# mcu.net
KiCad netlist of a schematic drawn in Altium Designer
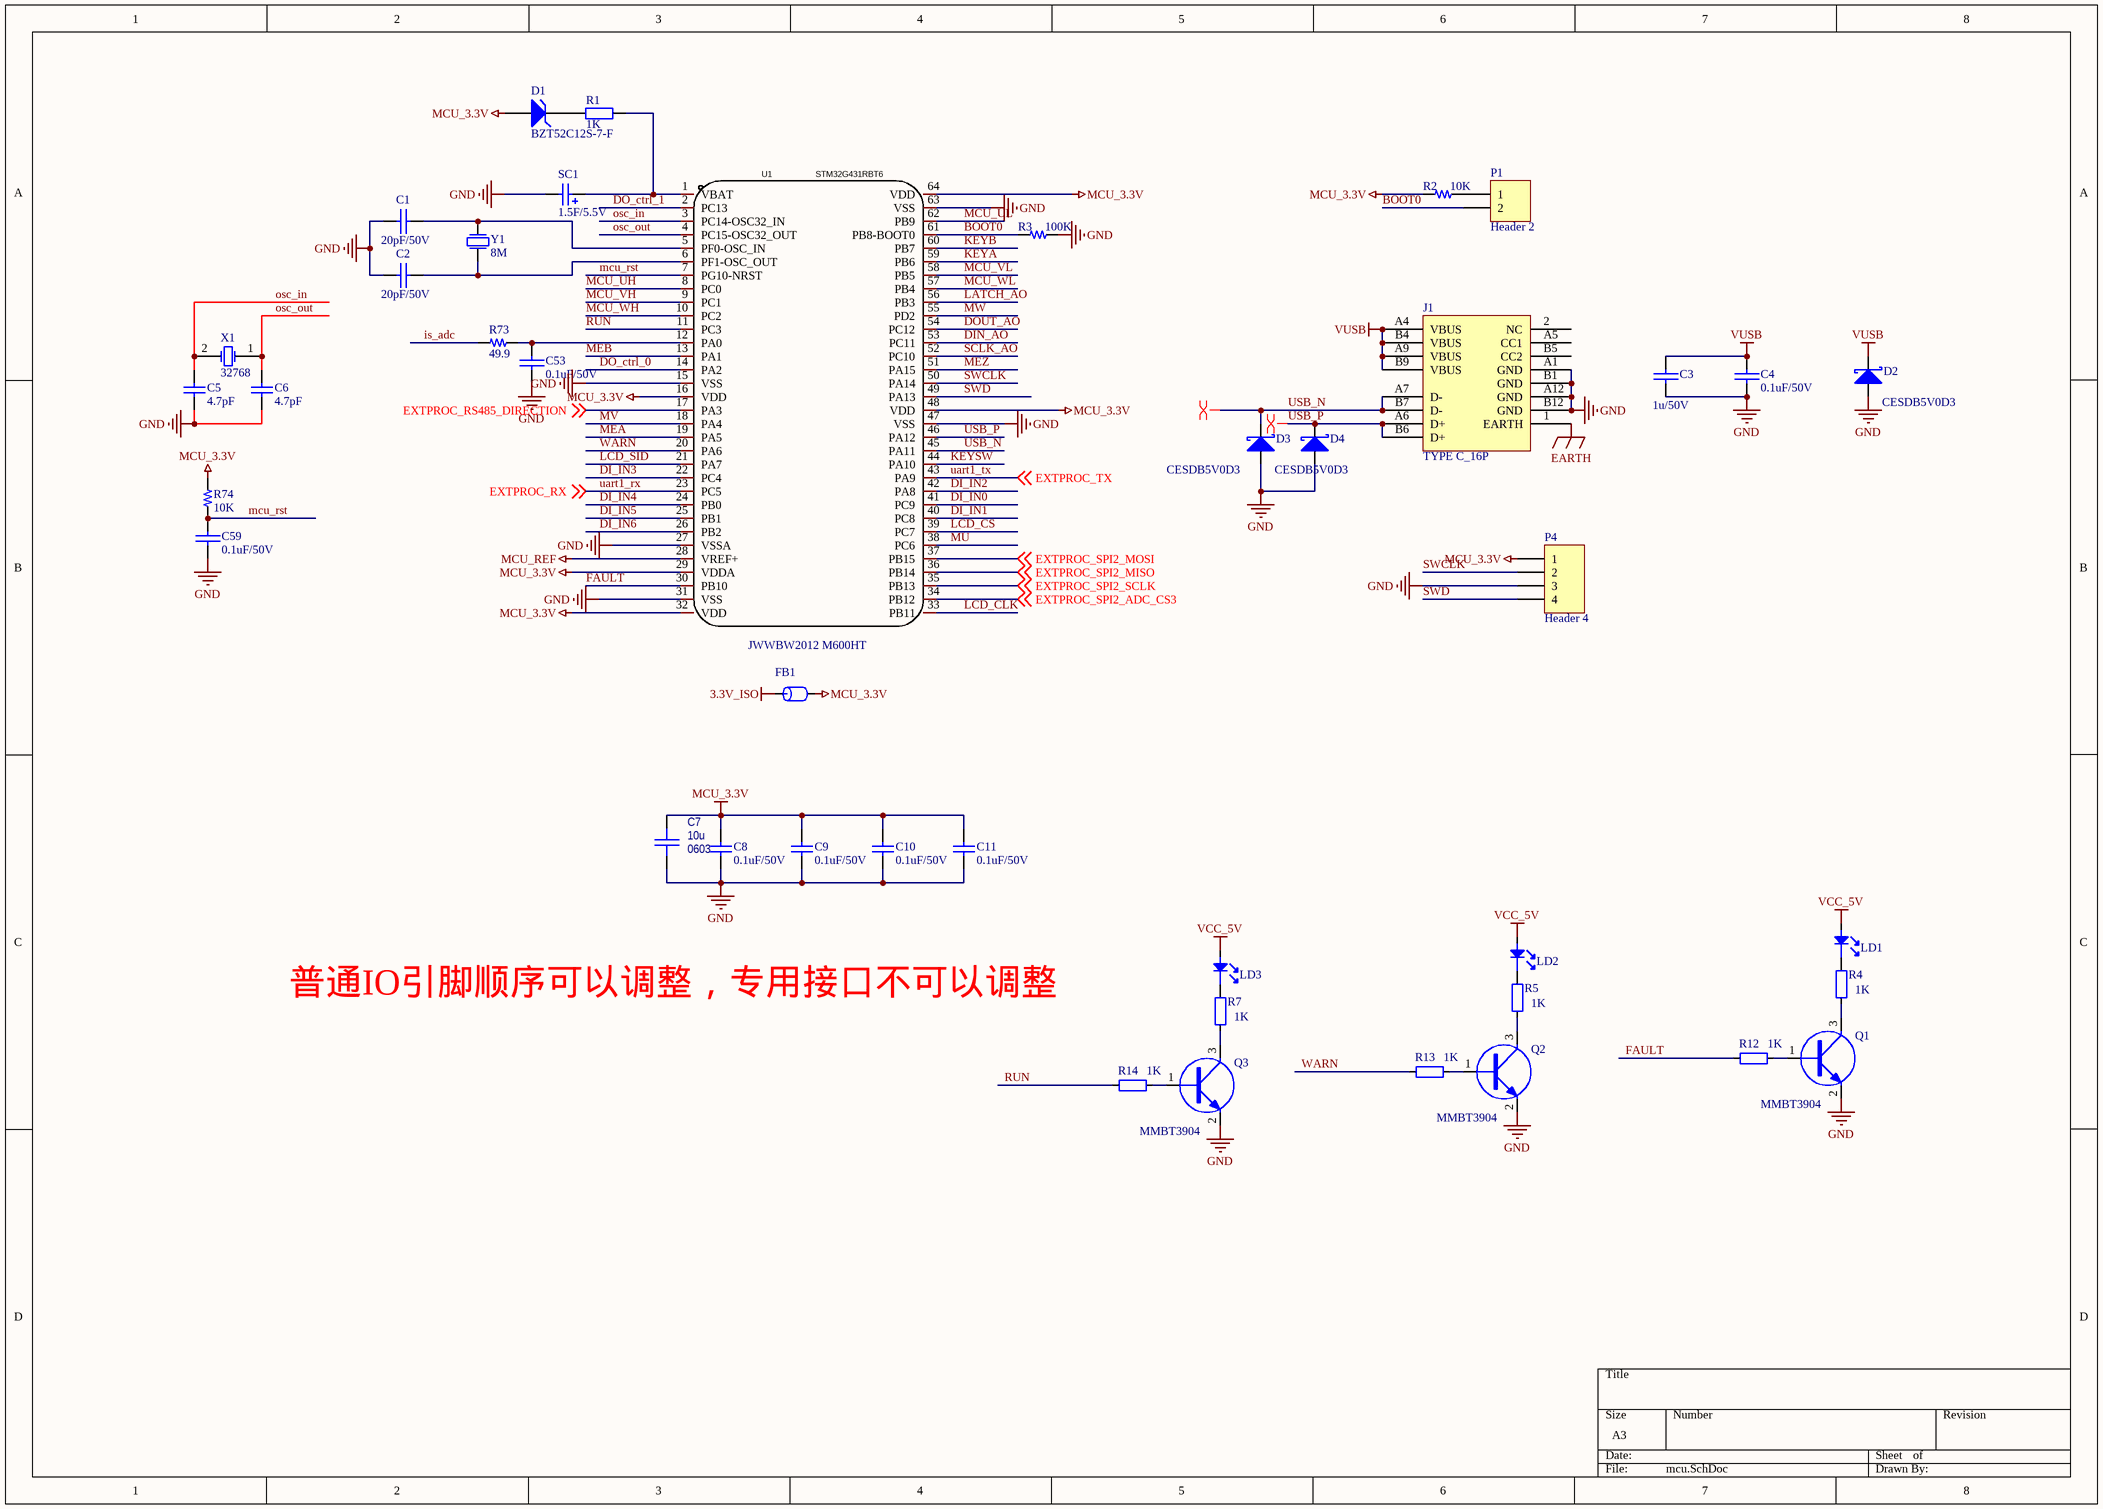
[diagram p0: mcu.SchDoc]

(export (version "E")
  (design (tool "Eeschema 10.0.6"))
  (components
    (comp (ref "C1")
      (value "20pF/50V")
      (footprint "0603C")
      (fields (field (name "Comment") "20pF/25V"))
      (libsource (lib "SM") (part "CAP"))
    )
    (comp (ref "C2")
      (value "20pF/50V")
      (footprint "0603C")
      (fields (field (name "Comment") "20pF/25V"))
      (libsource (lib "SM") (part "CAP"))
    )
    (comp (ref "C3")
      (value "1u/50V")
      (footprint "0603C")
      (fields (field (name "Comment") "1uF/25V"))
      (libsource (lib "SM") (part "CAP"))
    )
    (comp (ref "C4") (value "0.1uF/50V") (footprint "0603C") (libsource (lib "SM") (part "CAP")))
    (comp (ref "C5")
      (value "4.7pF")
      (footprint "0603C")
      (description "Capacitor")
      (fields (field (name "PUBLISHER") "Altium Limited"))
      (libsource (lib "Miscellaneous Devices") (part "Cap"))
    )
    (comp (ref "C6")
      (value "4.7pF")
      (footprint "0603C")
      (description "Capacitor")
      (fields (field (name "PUBLISHER") "Altium Limited"))
      (libsource (lib "Miscellaneous Devices") (part "Cap"))
    )
    (comp (ref "C7")
      (value "10u")
      (footprint "CAPC1608X092N_0603")
      (description "Capacitor, MLCC")
      (fields
        (field (name "MANUFACTURER") "Murata Electronics")
        (field (name "PARTNUMBER") "GRM188R61A106KE69D")
        (field (name "PACKAGE") "0603")
      )
      (libsource (lib "Karl") (part "Capacitor_0603"))
    )
    (comp (ref "C8")
      (value "0.1uF/50V")
      (footprint "0603C")
      (description "Capacitor")
      (fields (field (name "PUBLISHER") "Altium Limited"))
      (libsource (lib "Miscellaneous Devices") (part "Cap"))
    )
    (comp (ref "C9")
      (value "0.1uF/50V")
      (footprint "0603C")
      (description "Capacitor")
      (fields (field (name "PUBLISHER") "Altium Limited"))
      (libsource (lib "Miscellaneous Devices") (part "Cap"))
    )
    (comp (ref "C10")
      (value "0.1uF/50V")
      (footprint "0603C")
      (description "Capacitor")
      (fields (field (name "PUBLISHER") "Altium Limited"))
      (libsource (lib "Miscellaneous Devices") (part "Cap"))
    )
    (comp (ref "C11")
      (value "0.1uF/50V")
      (footprint "0603C")
      (description "Capacitor")
      (fields (field (name "PUBLISHER") "Altium Limited"))
      (libsource (lib "Miscellaneous Devices") (part "Cap"))
    )
    (comp (ref "C53") (value "0.1uF/50V") (footprint "0603C") (libsource (lib "SM") (part "CAP")))
    (comp (ref "C59") (value "0.1uF/50V") (footprint "0603C") (libsource (lib "SM") (part "CAP")))
    (comp (ref "D1")
      (value "BZT52C12S-7-F")
      (footprint "DIOD-SOD323-2_V")
      (libsource (lib "Bogen") (part "BZT52C12S-7-F"))
    )
    (comp (ref "D2") (value "CESDB5V0D3") (footprint "SOD323") (libsource (lib "*") (part "DIODE S")))
    (comp (ref "D3") (value "CESDB5V0D3") (footprint "SOD323") (libsource (lib "*") (part "DIODE S")))
    (comp (ref "D4") (value "CESDB5V0D3") (footprint "SOD323") (libsource (lib "*") (part "DIODE S")))
    (comp (ref "FB1")
      (value "JWWBW2012 M600HT")
      (footprint "0805R")
      (libsource (lib "Schlib_20110825") (part "FB"))
    )
    (comp (ref "J1")
      (value "TYPE C_16P")
      (footprint "TYPEC_16P")
      (libsource (lib "Schlib_20110825") (part "TYPE C_16P"))
    )
    (comp (ref "LD1")
      (value "LED_Green_19-217")
      (footprint "0603led")
      (libsource (lib "RC_M_D_00") (part "LED_Green_19-217"))
    )
    (comp (ref "LD2")
      (value "LED_Green_19-217")
      (footprint "0603led")
      (libsource (lib "RC_M_D_00") (part "LED_Green_19-217"))
    )
    (comp (ref "LD3")
      (value "LED_Green_19-217")
      (footprint "0603led")
      (libsource (lib "RC_M_D_00") (part "LED_Green_19-217"))
    )
    (comp (ref "P1")
      (value "Header 2")
      (footprint "HDR1X2")
      (fields (field (name "PUBLISHER") "Altium Limited"))
      (libsource (lib "Miscellaneous Connectors") (part "Header 2"))
    )
    (comp (ref "P4")
      (value "Header 4")
      (footprint "HDR1X4")
      (fields (field (name "PUBLISHER") "Altium Limited"))
      (libsource (lib "Miscellaneous Connectors") (part "Header 4"))
    )
    (comp (ref "Q1")
      (value "MMBT3904")
      (footprint "SOT23-3")
      (libsource (lib "CenLib") (part "NPN_MMBT3904"))
    )
    (comp (ref "Q2")
      (value "MMBT3904")
      (footprint "SOT23-3")
      (libsource (lib "CenLib") (part "NPN_MMBT3904"))
    )
    (comp (ref "Q3")
      (value "MMBT3904")
      (footprint "SOT23-3")
      (libsource (lib "CenLib") (part "NPN_MMBT3904"))
    )
    (comp (ref "R1") (value "1K") (footprint "0603R") (libsource (lib "MQlibrary") (part "Res0805M")))
    (comp (ref "R2") (value "10K") (footprint "0603R") (libsource (lib "JRJ_1") (part "R")))
    (comp (ref "R3") (value "100K") (footprint "0603R") (libsource (lib "JRJ_1") (part "R")))
    (comp (ref "R4") (value "1K") (footprint "0603r") (libsource (lib "RC_M_D_00") (part "RES0603")))
    (comp (ref "R5") (value "1K") (footprint "0603r") (libsource (lib "RC_M_D_00") (part "RES0603")))
    (comp (ref "R7") (value "1K") (footprint "0603r") (libsource (lib "RC_M_D_00") (part "RES0603")))
    (comp (ref "R12") (value "1K") (footprint "0603r") (libsource (lib "RC_M_D_00") (part "RES0603")))
    (comp (ref "R13") (value "1K") (footprint "0603r") (libsource (lib "RC_M_D_00") (part "RES0603")))
    (comp (ref "R14") (value "1K") (footprint "0603r") (libsource (lib "RC_M_D_00") (part "RES0603")))
    (comp (ref "R73") (value "49.9") (footprint "0603R") (libsource (lib "JRJ_1") (part "R")))
    (comp (ref "R74") (value "10K") (footprint "0603R") (libsource (lib "JRJ_1") (part "R")))
    (comp (ref "SC1")
      (value "1.5F/5.5V")
      (footprint "CAP-TH_DMS3R3224")
      (description "Polarized Capacitor (Axial)")
      (fields (field (name "PUBLISHER") "Altium Limited"))
      (libsource (lib "Miscellaneous Devices") (part "Cap Pol2"))
    )
    (comp (ref "U1")
      (value "STM32G431RBT6")
      (footprint "LQFP-64")
      (fields (field (name "MANUFACTURER") "ST(意法半导体)"))
      (libsource (lib "altium-import") (part "root_0_STM32G431RBT6_"))
    )
    (comp (ref "X1")
      (value "32768")
      (footprint "A")
      (description "Crystal Oscillator")
      (fields (field (name "PUBLISHER") "Altium Limited"))
      (libsource (lib "Miscellaneous Devices") (part "XTAL"))
    )
    (comp (ref "Y1") (value "8M") (footprint "CRAY_5032") (libsource (lib "") (part "XTAL_1")))
  )
  (nets
    (net (code "1") (name "/BOOT0") (class "Default")
      (node (ref "P1") (pin "2") (pinfunction "2_2") (pintype "passive"))
      (node (ref "R3") (pin "1") (pintype "passive"))
      (node (ref "U1") (pin "61") (pinfunction "PB8-BOOT0_61") (pintype "passive"))
    )
    (net (code "2") (name "/DIN_AO") (class "Default")
      (node (ref "U1") (pin "53") (pinfunction "PC11_53") (pintype "passive"))
    )
    (net (code "3") (name "/DI_IN0") (class "Default")
      (node (ref "U1") (pin "41") (pinfunction "PC9_41") (pintype "passive"))
    )
    (net (code "4") (name "/DI_IN1") (class "Default")
      (node (ref "U1") (pin "40") (pinfunction "PC8_40") (pintype "passive"))
    )
    (net (code "5") (name "/DI_IN2") (class "Default")
      (node (ref "U1") (pin "42") (pinfunction "PA8_42") (pintype "passive"))
    )
    (net (code "6") (name "/DI_IN3") (class "Default")
      (node (ref "U1") (pin "22") (pinfunction "PC4_22") (pintype "passive"))
    )
    (net (code "7") (name "/DI_IN4") (class "Default")
      (node (ref "U1") (pin "24") (pinfunction "PB0_24") (pintype "passive"))
    )
    (net (code "8") (name "/DI_IN5") (class "Default")
      (node (ref "U1") (pin "25") (pinfunction "PB1_25") (pintype "passive"))
    )
    (net (code "9") (name "/DI_IN6") (class "Default")
      (node (ref "U1") (pin "26") (pinfunction "PB2_26") (pintype "passive"))
    )
    (net (code "10") (name "/DOUT_AO") (class "Default")
      (node (ref "U1") (pin "54") (pinfunction "PC12_54") (pintype "passive"))
    )
    (net (code "11") (name "/DO_ctrl_0") (class "Default")
      (node (ref "U1") (pin "14") (pinfunction "PA2_14") (pintype "passive"))
    )
    (net (code "12") (name "/DO_ctrl_1") (class "Default")
      (node (ref "U1") (pin "2") (pinfunction "PC13_2") (pintype "passive"))
    )
    (net (code "13") (name "/FAULT") (class "Default")
      (node (ref "R12") (pin "1") (pinfunction "1_1") (pintype "passive"))
      (node (ref "U1") (pin "30") (pinfunction "PB10_30") (pintype "passive"))
    )
    (net (code "14") (name "/KEYA") (class "Default")
      (node (ref "U1") (pin "59") (pinfunction "PB6_59") (pintype "passive"))
    )
    (net (code "15") (name "/KEYB") (class "Default")
      (node (ref "U1") (pin "60") (pinfunction "PB7_60") (pintype "passive"))
    )
    (net (code "16") (name "/KEYSW") (class "Default")
      (node (ref "U1") (pin "44") (pinfunction "PA10_44") (pintype "passive"))
    )
    (net (code "17") (name "/LATCH_AO") (class "Default")
      (node (ref "U1") (pin "56") (pinfunction "PB3_56") (pintype "passive"))
    )
    (net (code "18") (name "/LCD_CLK") (class "Default")
      (node (ref "U1") (pin "33") (pinfunction "PB11_33") (pintype "passive"))
    )
    (net (code "19") (name "/LCD_CS") (class "Default")
      (node (ref "U1") (pin "39") (pinfunction "PC7_39") (pintype "passive"))
    )
    (net (code "20") (name "/LCD_SID") (class "Default")
      (node (ref "U1") (pin "21") (pinfunction "PA7_21") (pintype "passive"))
    )
    (net (code "21") (name "/MCU_UH") (class "Default")
      (node (ref "U1") (pin "8") (pinfunction "PC0_8") (pintype "passive"))
    )
    (net (code "22") (name "/MCU_UL") (class "Default")
      (node (ref "U1") (pin "62") (pinfunction "PB9_62") (pintype "passive"))
    )
    (net (code "23") (name "/MCU_VH") (class "Default")
      (node (ref "U1") (pin "9") (pinfunction "PC1_9") (pintype "passive"))
    )
    (net (code "24") (name "/MCU_VL") (class "Default")
      (node (ref "U1") (pin "58") (pinfunction "PB5_58") (pintype "passive"))
    )
    (net (code "25") (name "/MCU_WH") (class "Default")
      (node (ref "U1") (pin "10") (pinfunction "PC2_10") (pintype "passive"))
    )
    (net (code "26") (name "/MCU_WL") (class "Default")
      (node (ref "U1") (pin "57") (pinfunction "PB4_57") (pintype "passive"))
    )
    (net (code "27") (name "/MEA") (class "Default")
      (node (ref "U1") (pin "19") (pinfunction "PA5_19") (pintype "passive"))
    )
    (net (code "28") (name "/MEB") (class "Default")
      (node (ref "U1") (pin "13") (pinfunction "PA1_13") (pintype "passive"))
    )
    (net (code "29") (name "/MEZ") (class "Default")
      (node (ref "U1") (pin "51") (pinfunction "PA15_51") (pintype "passive"))
    )
    (net (code "30") (name "/MU") (class "Default")
      (node (ref "U1") (pin "38") (pinfunction "PC6_38") (pintype "passive"))
    )
    (net (code "31") (name "/MV") (class "Default")
      (node (ref "U1") (pin "18") (pinfunction "PA4_18") (pintype "passive"))
    )
    (net (code "32") (name "/MW") (class "Default")
      (node (ref "U1") (pin "55") (pinfunction "PD2_55") (pintype "passive"))
    )
    (net (code "33") (name "/RUN") (class "Default")
      (node (ref "R14") (pin "1") (pinfunction "1_1") (pintype "passive"))
      (node (ref "U1") (pin "11") (pinfunction "PC3_11") (pintype "passive"))
    )
    (net (code "34") (name "/SCLK_AO") (class "Default")
      (node (ref "U1") (pin "52") (pinfunction "PC10_52") (pintype "passive"))
    )
    (net (code "35") (name "/SWCLK") (class "Default")
      (node (ref "P4") (pin "2") (pinfunction "2_2") (pintype "passive"))
      (node (ref "U1") (pin "50") (pinfunction "PA14_50") (pintype "passive"))
    )
    (net (code "36") (name "/SWD") (class "Default")
      (node (ref "P4") (pin "4") (pinfunction "4_4") (pintype "passive"))
      (node (ref "U1") (pin "49") (pinfunction "PA13_49") (pintype "passive"))
    )
    (net (code "37") (name "/USB_N") (class "Default")
      (node (ref "D3") (pin "2") (pinfunction "K_2") (pintype "passive"))
      (node (ref "J1") (pin "A7") (pinfunction "D-_A7") (pintype "passive"))
      (node (ref "J1") (pin "B7") (pinfunction "D-_B7") (pintype "passive"))
      (node (ref "U1") (pin "45") (pinfunction "PA11_45") (pintype "passive"))
    )
    (net (code "38") (name "/USB_P") (class "Default")
      (node (ref "D4") (pin "2") (pinfunction "K_2") (pintype "passive"))
      (node (ref "J1") (pin "A6") (pinfunction "D+_A6") (pintype "passive"))
      (node (ref "J1") (pin "B6") (pinfunction "D+_B6") (pintype "passive"))
      (node (ref "U1") (pin "46") (pinfunction "PA12_46") (pintype "passive"))
    )
    (net (code "39") (name "/WARN") (class "Default")
      (node (ref "R13") (pin "1") (pinfunction "1_1") (pintype "passive"))
      (node (ref "U1") (pin "20") (pinfunction "PA6_20") (pintype "passive"))
    )
    (net (code "40") (name "/is_adc") (class "Default") (node (ref "R73") (pin "1") (pintype "passive")))
    (net (code "41") (name "/mcu_rst") (class "Default")
      (node (ref "C59") (pin "2") (pinfunction "2_2") (pintype "passive"))
      (node (ref "R74") (pin "2") (pintype "passive"))
      (node (ref "U1") (pin "7") (pinfunction "PG10-NRST_7") (pintype "passive"))
    )
    (net (code "42") (name "/osc_in") (class "Default")
      (node (ref "C5") (pin "1") (pinfunction "1_1") (pintype "passive"))
      (node (ref "U1") (pin "3") (pinfunction "PC14-OSC32_IN_3") (pintype "passive"))
      (node (ref "X1") (pin "2") (pinfunction "OSC2_2") (pintype "passive"))
    )
    (net (code "43") (name "/osc_out") (class "Default")
      (node (ref "C6") (pin "1") (pinfunction "1_1") (pintype "passive"))
      (node (ref "U1") (pin "4") (pinfunction "PC15-OSC32_OUT_4") (pintype "passive"))
      (node (ref "X1") (pin "1") (pinfunction "OSC1_1") (pintype "passive"))
    )
    (net (code "44") (name "3.3V_ISO") (class "Default") (node (ref "FB1") (pin "1") (pintype "passive")))
    (net (code "45") (name "EARTH") (class "Default")
      (node (ref "J1") (pin "1") (pinfunction "EARTH_1") (pintype "passive"))
    )
    (net (code "46") (name "EXTPROC_RS485_DIRECTION") (class "Default")
      (node (ref "U1") (pin "17") (pinfunction "PA3_17") (pintype "passive"))
    )
    (net (code "47") (name "EXTPROC_RX") (class "Default")
      (node (ref "U1") (pin "23") (pinfunction "PC5_23") (pintype "passive"))
    )
    (net (code "48") (name "EXTPROC_SPI2_ADC_CS3") (class "Default")
      (node (ref "U1") (pin "34") (pinfunction "PB12_34") (pintype "passive"))
    )
    (net (code "49") (name "EXTPROC_SPI2_MISO") (class "Default")
      (node (ref "U1") (pin "36") (pinfunction "PB14_36") (pintype "passive"))
    )
    (net (code "50") (name "EXTPROC_SPI2_MOSI") (class "Default")
      (node (ref "U1") (pin "37") (pinfunction "PB15_37") (pintype "passive"))
    )
    (net (code "51") (name "EXTPROC_SPI2_SCLK") (class "Default")
      (node (ref "U1") (pin "35") (pinfunction "PB13_35") (pintype "passive"))
    )
    (net (code "52") (name "EXTPROC_TX") (class "Default")
      (node (ref "U1") (pin "43") (pinfunction "PA9_43") (pintype "passive"))
    )
    (net (code "53") (name "GND") (class "Default")
      (node (ref "C1") (pin "2") (pinfunction "2_2") (pintype "passive"))
      (node (ref "C10") (pin "1") (pinfunction "1_1") (pintype "passive"))
      (node (ref "C11") (pin "1") (pinfunction "1_1") (pintype "passive"))
      (node (ref "C2") (pin "2") (pinfunction "2_2") (pintype "passive"))
      (node (ref "C3") (pin "1") (pinfunction "1_1") (pintype "passive"))
      (node (ref "C4") (pin "1") (pinfunction "1_1") (pintype "passive"))
      (node (ref "C5") (pin "2") (pinfunction "2_2") (pintype "passive"))
      (node (ref "C53") (pin "1") (pinfunction "1_1") (pintype "passive"))
      (node (ref "C59") (pin "1") (pinfunction "1_1") (pintype "passive"))
      (node (ref "C6") (pin "2") (pinfunction "2_2") (pintype "passive"))
      (node (ref "C7") (pin "2") (pinfunction "2_2") (pintype "passive"))
      (node (ref "C8") (pin "1") (pinfunction "1_1") (pintype "passive"))
      (node (ref "C9") (pin "1") (pinfunction "1_1") (pintype "passive"))
      (node (ref "D2") (pin "1") (pinfunction "A_1") (pintype "passive"))
      (node (ref "D3") (pin "1") (pinfunction "A_1") (pintype "passive"))
      (node (ref "D4") (pin "1") (pinfunction "A_1") (pintype "passive"))
      (node (ref "J1") (pin "A1") (pinfunction "GND_A1") (pintype "passive"))
      (node (ref "J1") (pin "A12") (pinfunction "GND_A12") (pintype "passive"))
      (node (ref "J1") (pin "B1") (pinfunction "GND_B1") (pintype "passive"))
      (node (ref "J1") (pin "B12") (pinfunction "GND_B12") (pintype "passive"))
      (node (ref "P4") (pin "3") (pinfunction "3_3") (pintype "passive"))
      (node (ref "Q1") (pin "2") (pinfunction "E_2") (pintype "passive"))
      (node (ref "Q2") (pin "2") (pinfunction "E_2") (pintype "passive"))
      (node (ref "Q3") (pin "2") (pinfunction "E_2") (pintype "passive"))
      (node (ref "R3") (pin "2") (pintype "passive"))
      (node (ref "SC1") (pin "2") (pinfunction "2_2") (pintype "passive"))
      (node (ref "U1") (pin "15") (pinfunction "VSS_15") (pintype "passive"))
      (node (ref "U1") (pin "27") (pinfunction "VSSA_27") (pintype "passive"))
      (node (ref "U1") (pin "31") (pinfunction "VSS_31") (pintype "passive"))
      (node (ref "U1") (pin "47") (pinfunction "VSS_47") (pintype "passive"))
      (node (ref "U1") (pin "63") (pinfunction "VSS_63") (pintype "passive"))
    )
    (net (code "54") (name "MCU_3.3V") (class "Default")
      (node (ref "C10") (pin "2") (pinfunction "2_2") (pintype "passive"))
      (node (ref "C11") (pin "2") (pinfunction "2_2") (pintype "passive"))
      (node (ref "C7") (pin "1") (pinfunction "1_1") (pintype "passive"))
      (node (ref "C8") (pin "2") (pinfunction "2_2") (pintype "passive"))
      (node (ref "C9") (pin "2") (pinfunction "2_2") (pintype "passive"))
      (node (ref "D1") (pin "1") (pinfunction "A_1") (pintype "passive"))
      (node (ref "FB1") (pin "2") (pintype "passive"))
      (node (ref "P4") (pin "1") (pinfunction "1_1") (pintype "passive"))
      (node (ref "R2") (pin "1") (pintype "passive"))
      (node (ref "R74") (pin "1") (pintype "passive"))
      (node (ref "U1") (pin "16") (pinfunction "VDD_16") (pintype "passive"))
      (node (ref "U1") (pin "29") (pinfunction "VDDA_29") (pintype "passive"))
      (node (ref "U1") (pin "32") (pinfunction "VDD_32") (pintype "passive"))
      (node (ref "U1") (pin "48") (pinfunction "VDD_48") (pintype "passive"))
      (node (ref "U1") (pin "64") (pinfunction "VDD_64") (pintype "passive"))
    )
    (net (code "55") (name "MCU_REF") (class "Default")
      (node (ref "U1") (pin "28") (pinfunction "VREF+_28") (pintype "passive"))
    )
    (net (code "56") (name "Net-(D1-K)") (class "Default")
      (node (ref "D1") (pin "2") (pinfunction "K_2") (pintype "passive"))
      (node (ref "R1") (pin "1") (pinfunction "1_1") (pintype "passive"))
    )
    (net (code "57") (name "Net-(LD1-Pad2)") (class "Default")
      (node (ref "LD1") (pin "2") (pinfunction "2_2") (pintype "passive"))
      (node (ref "R4") (pin "1") (pinfunction "1_1") (pintype "passive"))
    )
    (net (code "58") (name "Net-(LD2-Pad2)") (class "Default")
      (node (ref "LD2") (pin "2") (pinfunction "2_2") (pintype "passive"))
      (node (ref "R5") (pin "1") (pinfunction "1_1") (pintype "passive"))
    )
    (net (code "59") (name "Net-(LD3-Pad2)") (class "Default")
      (node (ref "LD3") (pin "2") (pinfunction "2_2") (pintype "passive"))
      (node (ref "R7") (pin "1") (pinfunction "1_1") (pintype "passive"))
    )
    (net (code "60") (name "Net-(P1-Pad1)") (class "Default")
      (node (ref "P1") (pin "1") (pinfunction "1_1") (pintype "passive"))
      (node (ref "R2") (pin "2") (pintype "passive"))
    )
    (net (code "61") (name "Net-(Q1-B)") (class "Default")
      (node (ref "Q1") (pin "1") (pinfunction "B_1") (pintype "passive"))
      (node (ref "R12") (pin "2") (pinfunction "2_2") (pintype "passive"))
    )
    (net (code "62") (name "Net-(Q1-C)") (class "Default")
      (node (ref "Q1") (pin "3") (pinfunction "C_3") (pintype "passive"))
      (node (ref "R4") (pin "2") (pinfunction "2_2") (pintype "passive"))
    )
    (net (code "63") (name "Net-(Q2-B)") (class "Default")
      (node (ref "Q2") (pin "1") (pinfunction "B_1") (pintype "passive"))
      (node (ref "R13") (pin "2") (pinfunction "2_2") (pintype "passive"))
    )
    (net (code "64") (name "Net-(Q2-C)") (class "Default")
      (node (ref "Q2") (pin "3") (pinfunction "C_3") (pintype "passive"))
      (node (ref "R5") (pin "2") (pinfunction "2_2") (pintype "passive"))
    )
    (net (code "65") (name "Net-(Q3-B)") (class "Default")
      (node (ref "Q3") (pin "1") (pinfunction "B_1") (pintype "passive"))
      (node (ref "R14") (pin "2") (pinfunction "2_2") (pintype "passive"))
    )
    (net (code "66") (name "Net-(Q3-C)") (class "Default")
      (node (ref "Q3") (pin "3") (pinfunction "C_3") (pintype "passive"))
      (node (ref "R7") (pin "2") (pinfunction "2_2") (pintype "passive"))
    )
    (net (code "67") (name "Net-(U1-PA0)") (class "Default")
      (node (ref "C53") (pin "2") (pinfunction "2_2") (pintype "passive"))
      (node (ref "R73") (pin "2") (pintype "passive"))
      (node (ref "U1") (pin "12") (pinfunction "PA0_12") (pintype "passive"))
    )
    (net (code "68") (name "Net-(U1-PF0-OSC_IN)") (class "Default")
      (node (ref "C1") (pin "1") (pinfunction "1_1") (pintype "passive"))
      (node (ref "U1") (pin "5") (pinfunction "PF0-OSC_IN_5") (pintype "passive"))
      (node (ref "Y1") (pin "1") (pinfunction "P1_1") (pintype "passive"))
    )
    (net (code "69") (name "Net-(U1-PF1-OSC_OUT)") (class "Default")
      (node (ref "C2") (pin "1") (pinfunction "1_1") (pintype "passive"))
      (node (ref "U1") (pin "6") (pinfunction "PF1-OSC_OUT_6") (pintype "passive"))
      (node (ref "Y1") (pin "2") (pinfunction "P2_2") (pintype "passive"))
    )
    (net (code "70") (name "Net-(U1-VBAT)") (class "Default")
      (node (ref "R1") (pin "2") (pinfunction "2_2") (pintype "passive"))
      (node (ref "SC1") (pin "1") (pinfunction "1_1") (pintype "passive"))
      (node (ref "U1") (pin "1") (pinfunction "VBAT_1") (pintype "passive"))
    )
    (net (code "71") (name "VCC_5V") (class "Default")
      (node (ref "LD1") (pin "1") (pinfunction "1_1") (pintype "passive"))
      (node (ref "LD2") (pin "1") (pinfunction "1_1") (pintype "passive"))
      (node (ref "LD3") (pin "1") (pinfunction "1_1") (pintype "passive"))
    )
    (net (code "72") (name "VUSB") (class "Default")
      (node (ref "C3") (pin "2") (pinfunction "2_2") (pintype "passive"))
      (node (ref "C4") (pin "2") (pinfunction "2_2") (pintype "passive"))
      (node (ref "D2") (pin "2") (pinfunction "K_2") (pintype "passive"))
      (node (ref "J1") (pin "A4") (pinfunction "VBUS_A4") (pintype "passive"))
      (node (ref "J1") (pin "A9") (pinfunction "VBUS_A9") (pintype "passive"))
      (node (ref "J1") (pin "B4") (pinfunction "VBUS_B4") (pintype "passive"))
      (node (ref "J1") (pin "B9") (pinfunction "VBUS_B9") (pintype "passive"))
    )
    (net (code "73") (name "unconnected-(J1-CC1-PadA5)") (class "Default")
      (node (ref "J1") (pin "A5") (pinfunction "CC1_A5") (pintype "passive"))
    )
    (net (code "74") (name "unconnected-(J1-CC2-PadB5)") (class "Default")
      (node (ref "J1") (pin "B5") (pinfunction "CC2_B5") (pintype "passive"))
    )
    (net (code "75") (name "unconnected-(J1-NC-Pad2)") (class "Default")
      (node (ref "J1") (pin "2") (pinfunction "NC_2") (pintype "passive"))
    )
  )
)
